# atmega.net
KiCad netlist of a schematic drawn in Altium Designer
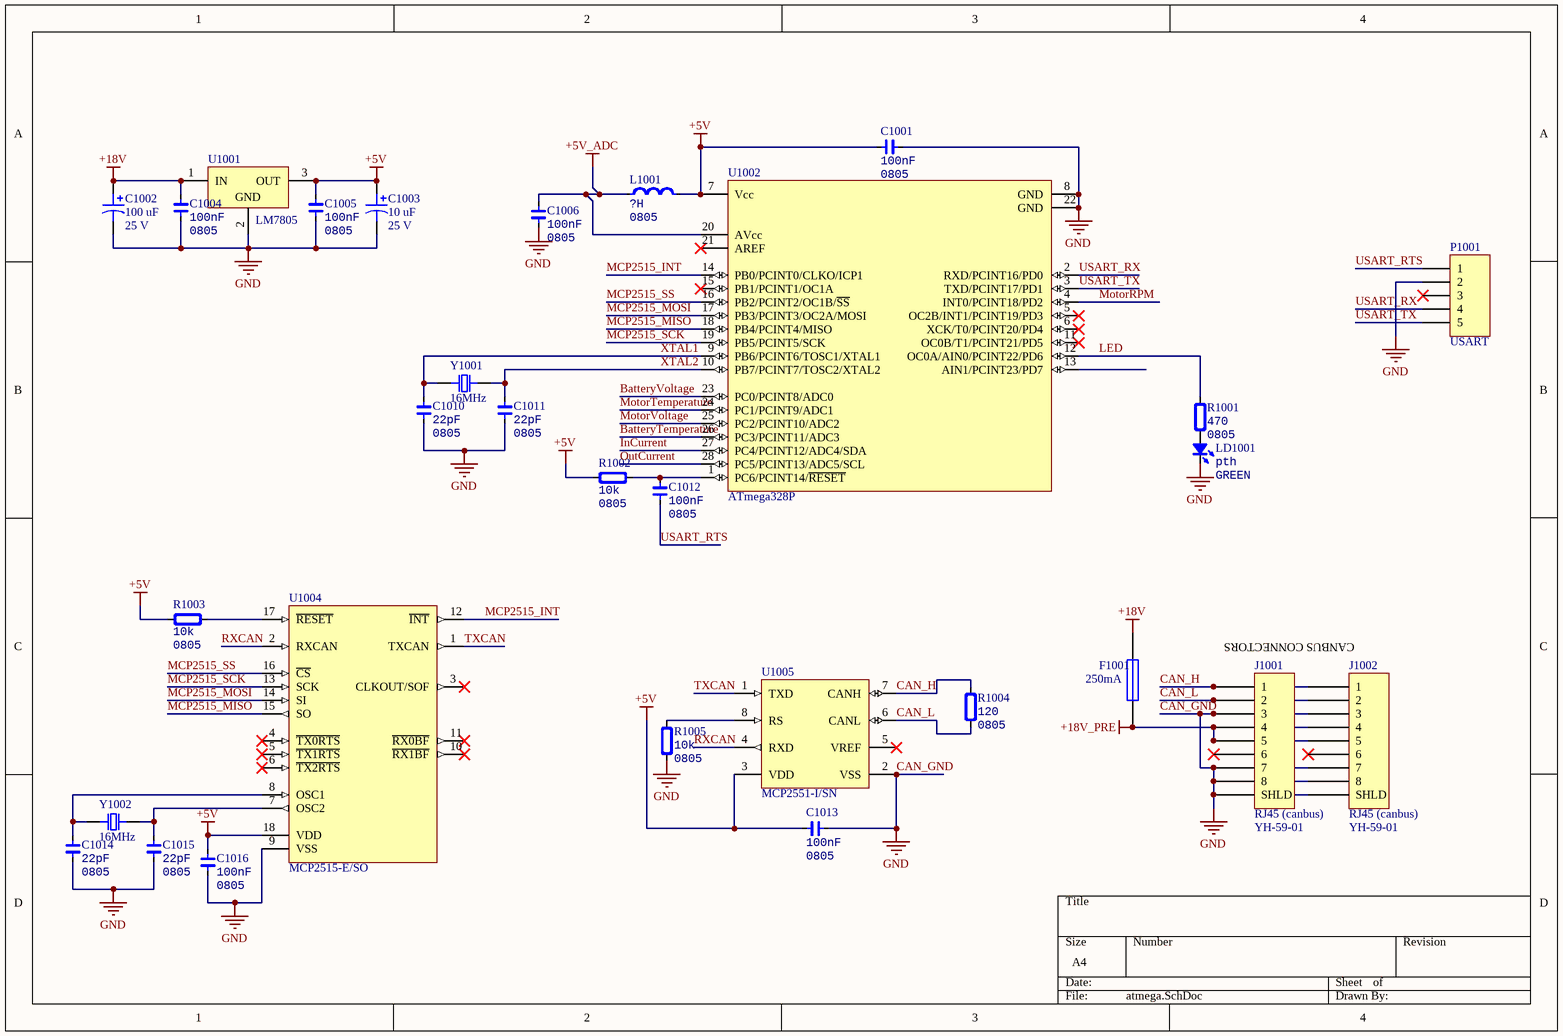
[diagram p0: atmega.SchDoc]

(export (version "E")
  (design (tool "Eeschema 10.0.6"))
  (components
    (comp (ref "C1001")
      (value "100nF")
      (footprint "Zenite_Footprints:0805C")
      (description "Capacitor")
      (fields (field (name "TYPE") "0805"))
      (libsource (lib "") (part "Cap_0805_1"))
    )
    (comp (ref "C1002")
      (value "100 uF")
      (footprint "CP3.5mm-8.0mm")
      (description "Solid Aluminum Capacitor with Organic Semiconductor Electrolyte: 100uF, 10V, Bulk Pack")
      (fields (field (name "VOLTAGE") "25 V") (field (name "Comment") "CapacitorPol"))
      (libsource (lib "R2R - Nova") (part "CapacitorPol"))
    )
    (comp (ref "C1003")
      (value "10 uF")
      (footprint "CP3.5mm-8.0mm")
      (description "Solid Aluminum Capacitor with Organic Semiconductor Electrolyte: 100uF, 10V, Bulk Pack")
      (fields (field (name "VOLTAGE") "25 V") (field (name "Comment") "CapacitorPol"))
      (libsource (lib "R2R - Nova") (part "CapacitorPol"))
    )
    (comp (ref "C1004")
      (value "100nF")
      (footprint "Zenite_Footprints:0805C")
      (description "Capacitor")
      (fields (field (name "TYPE") "0805"))
      (libsource (lib "SCH_Passive") (part "Cap_0805"))
    )
    (comp (ref "C1005")
      (value "100nF")
      (footprint "Zenite_Footprints:0805C")
      (description "Capacitor")
      (fields (field (name "TYPE") "0805"))
      (libsource (lib "SCH_Passive") (part "Cap_0805"))
    )
    (comp (ref "C1006")
      (value "100nF")
      (footprint "Zenite_Footprints:0805C")
      (description "Capacitor")
      (fields (field (name "TYPE") "0805"))
      (libsource (lib "SCH_Passive") (part "Cap_0805"))
    )
    (comp (ref "C1010")
      (value "22pF")
      (footprint "Zenite_Footprints:0805C")
      (description "Capacitor")
      (fields (field (name "TYPE") "0805"))
      (libsource (lib "SCH_Passive") (part "Cap_0805"))
    )
    (comp (ref "C1011")
      (value "22pF")
      (footprint "Zenite_Footprints:0805C")
      (description "Capacitor")
      (fields (field (name "TYPE") "0805"))
      (libsource (lib "SCH_Passive") (part "Cap_0805"))
    )
    (comp (ref "C1012")
      (value "100nF")
      (footprint "Zenite_Footprints:0805C")
      (description "Capacitor")
      (fields (field (name "TYPE") "0805"))
      (libsource (lib "") (part "Cap_0805_2"))
    )
    (comp (ref "C1013")
      (value "100nF")
      (footprint "Zenite_Footprints:0805C")
      (description "Capacitor")
      (fields (field (name "TYPE") "0805"))
      (libsource (lib "") (part "Cap_0805_1"))
    )
    (comp (ref "C1014")
      (value "22pF")
      (footprint "Zenite_Footprints:0805C")
      (description "Capacitor")
      (fields (field (name "TYPE") "0805"))
      (libsource (lib "SCH_Passive") (part "Cap_0805"))
    )
    (comp (ref "C1015")
      (value "22pF")
      (footprint "Zenite_Footprints:0805C")
      (description "Capacitor")
      (fields (field (name "TYPE") "0805"))
      (libsource (lib "SCH_Passive") (part "Cap_0805"))
    )
    (comp (ref "C1016")
      (value "100nF")
      (footprint "Zenite_Footprints:0805C")
      (description "Capacitor")
      (fields (field (name "TYPE") "0805"))
      (libsource (lib "") (part "Cap_0805_2"))
    )
    (comp (ref "F1001")
      (value "250mA")
      (footprint "Porta Fusivel")
      (description "Fuse")
      (libsource (lib "Miscellaneous Devices") (part "Fuse 1"))
    )
    (comp (ref "J1001")
      (value "RJ45 (canbus)")
      (footprint "ASSMANN A-2004-2-4-LP/FS")
      (description "YH-59-01")
      (fields (field (name "ALTIUM_VALUE") "YH-59-01"))
      (libsource (lib "Connectors") (part "Modular Jack with Shield"))
    )
    (comp (ref "J1002")
      (value "RJ45 (canbus)")
      (footprint "ASSMANN A-2004-2-4-LP/FS")
      (description "YH-59-01")
      (fields (field (name "ALTIUM_VALUE") "YH-59-01"))
      (libsource (lib "Connectors") (part "Modular Jack with Shield"))
    )
    (comp (ref "L1001")
      (value "?H")
      (footprint "Zenite_Footprints:0805L")
      (description "Inductor")
      (fields (field (name "TYPE") "0805"))
      (libsource (lib "SCH_Passive") (part "Ind_0805"))
    )
    (comp (ref "LD1001")
      (value "GREEN")
      (footprint "LED3MM")
      (description "LED")
      (fields (field (name "TYPE") "pth"))
      (libsource (lib "SCH_Active") (part "LED_0805"))
    )
    (comp (ref "P1001")
      (value "USART")
      (footprint "Zenite_Footprints:HDR1X5")
      (description "Header, 5-Pin")
      (libsource (lib "R2R - Nova") (part "Header 5"))
    )
    (comp (ref "R1001")
      (value "470")
      (footprint "Zenite_Footprints:0805R")
      (description "Resistor")
      (fields (field (name "TYPE") "0805"))
      (libsource (lib "SCH_Passive") (part "Res_0805"))
    )
    (comp (ref "R1002")
      (value "10k")
      (footprint "Zenite_Footprints:0805R")
      (description "Resistor")
      (fields (field (name "TYPE") "0805"))
      (libsource (lib "SCH_Passive") (part "Res_0805"))
    )
    (comp (ref "R1003")
      (value "10k")
      (footprint "Zenite_Footprints:0805R")
      (description "Resistor")
      (fields (field (name "TYPE") "0805"))
      (libsource (lib "SCH_Passive") (part "Res_0805"))
    )
    (comp (ref "R1004")
      (value "120")
      (footprint "Zenite_Footprints:0805R")
      (description "Resistor")
      (fields (field (name "TYPE") "0805"))
      (libsource (lib "SCH_Passive") (part "Res_0805"))
    )
    (comp (ref "R1005")
      (value "10k")
      (footprint "Zenite_Footprints:0805R")
      (description "Resistor")
      (fields (field (name "TYPE") "0805"))
      (libsource (lib "SCH_Passive") (part "Res_0805"))
    )
    (comp (ref "U1001")
      (value "LM7805")
      (footprint "TO220_deitado")
      (description "Positive-Voltage Regulator")
      (libsource (lib "TI Power Mgt Voltage Regulator") (part "µA7805CKC"))
    )
    (comp (ref "U1002")
      (value "ATmega328P")
      (footprint "DIP28-300(100)")
      (libsource (lib "R2R - Nova") (part "ATmega328P"))
    )
    (comp (ref "U1004")
      (value "MCP2515-E/SO")
      (footprint "WSO18_L")
      (description "Stand-Alone CAN Controller With SPI Interface, 18-Pin SOIC, Extended Temperature")
      (libsource (lib "Altium Content Vault") (part "COM-CAN-MCP2515-18"))
    )
    (comp (ref "U1005")
      (value "MCP2551-I/SN")
      (footprint "SOIC08-150(50)")
      (libsource (lib "Altium Content Vault") (part "MCHP-MCP2551-SN8"))
    )
    (comp (ref "Y1001")
      (value "16MHz")
      (footprint "HC49-US-THT")
      (description "Crystal")
      (libsource (lib "R2R - Nova") (part "Crystal"))
    )
    (comp (ref "Y1002")
      (value "16MHz")
      (footprint "HC49-US-THT")
      (description "Crystal")
      (libsource (lib "R2R - Nova") (part "Crystal"))
    )
  )
  (nets
    (net (code "1") (name "+5V") (class "Default")
      (node (ref "C1001") (pin "1") (pinfunction "1_1") (pintype "passive"))
      (node (ref "C1003") (pin "1") (pinfunction "1_1") (pintype "passive"))
      (node (ref "C1005") (pin "2") (pinfunction "2_2") (pintype "passive"))
      (node (ref "C1013") (pin "1") (pinfunction "1_1") (pintype "passive"))
      (node (ref "C1016") (pin "1") (pinfunction "1_1") (pintype "passive"))
      (node (ref "L1001") (pin "2") (pinfunction "2_2") (pintype "passive"))
      (node (ref "R1002") (pin "1") (pinfunction "1_1") (pintype "passive"))
      (node (ref "R1003") (pin "1") (pinfunction "1_1") (pintype "passive"))
      (node (ref "U1001") (pin "3") (pinfunction "OUT_3") (pintype "power_in"))
      (node (ref "U1002") (pin "7") (pinfunction "Vcc_7") (pintype "passive"))
      (node (ref "U1004") (pin "18") (pinfunction "VDD_18") (pintype "power_in"))
      (node (ref "U1005") (pin "3") (pinfunction "VDD_3") (pintype "power_in"))
    )
    (net (code "2") (name "+5V_ADC") (class "Default")
      (node (ref "C1006") (pin "2") (pinfunction "2_2") (pintype "passive"))
      (node (ref "L1001") (pin "1") (pinfunction "1_1") (pintype "passive"))
      (node (ref "U1002") (pin "20") (pinfunction "AVcc_20") (pintype "passive"))
    )
    (net (code "3") (name "+18V") (class "Default")
      (node (ref "C1002") (pin "1") (pinfunction "1_1") (pintype "passive"))
      (node (ref "C1004") (pin "2") (pinfunction "2_2") (pintype "passive"))
      (node (ref "F1001") (pin "1") (pinfunction "1_1") (pintype "passive"))
      (node (ref "U1001") (pin "1") (pinfunction "IN_1") (pintype "power_in"))
    )
    (net (code "4") (name "+18V_PRE") (class "Default")
      (node (ref "F1001") (pin "2") (pinfunction "2_2") (pintype "passive"))
      (node (ref "J1001") (pin "4") (pinfunction "4_4") (pintype "passive"))
      (node (ref "J1001") (pin "5") (pinfunction "5_5") (pintype "passive"))
      (node (ref "J1002") (pin "4") (pinfunction "4_4") (pintype "passive"))
      (node (ref "J1002") (pin "5") (pinfunction "5_5") (pintype "passive"))
    )
    (net (code "5") (name "/BatteryTemperature") (class "Default")
      (node (ref "U1002") (pin "26") (pinfunction "PC3/PCINT11/ADC3_26") (pintype "bidirectional"))
    )
    (net (code "6") (name "/BatteryVoltage") (class "Default")
      (node (ref "U1002") (pin "23") (pinfunction "PC0/PCINT8/ADC0_23") (pintype "bidirectional"))
    )
    (net (code "7") (name "/CAN_H") (class "Default")
      (node (ref "J1001") (pin "1") (pinfunction "1_1") (pintype "passive"))
      (node (ref "J1002") (pin "1") (pinfunction "1_1") (pintype "passive"))
      (node (ref "R1004") (pin "2") (pinfunction "2_2") (pintype "passive"))
      (node (ref "U1005") (pin "7") (pinfunction "CANH_7") (pintype "bidirectional"))
    )
    (net (code "8") (name "/CAN_L") (class "Default")
      (node (ref "J1001") (pin "2") (pinfunction "2_2") (pintype "passive"))
      (node (ref "J1002") (pin "2") (pinfunction "2_2") (pintype "passive"))
      (node (ref "R1004") (pin "1") (pinfunction "1_1") (pintype "passive"))
      (node (ref "U1005") (pin "6") (pinfunction "CANL_6") (pintype "bidirectional"))
    )
    (net (code "9") (name "/InCurrent") (class "Default")
      (node (ref "U1002") (pin "27") (pinfunction "PC4/PCINT12/ADC4/SDA_27") (pintype "bidirectional"))
    )
    (net (code "10") (name "/LED") (class "Default")
      (node (ref "R1001") (pin "2") (pinfunction "2_2") (pintype "passive"))
      (node (ref "U1002") (pin "12") (pinfunction "OC0A/AIN0/PCINT22/PD6_12") (pintype "bidirectional"))
    )
    (net (code "11") (name "/MCP2515_INT") (class "Default")
      (node (ref "U1002") (pin "14") (pinfunction "PB0/PCINT0/CLKO/ICP1_14") (pintype "bidirectional"))
      (node (ref "U1004") (pin "12") (pinfunction "~{INT}_12") (pintype "output"))
    )
    (net (code "12") (name "/MCP2515_MISO") (class "Default")
      (node (ref "U1002") (pin "18") (pinfunction "PB4/PCINT4/MISO_18") (pintype "bidirectional"))
      (node (ref "U1004") (pin "15") (pinfunction "SO_15") (pintype "output"))
    )
    (net (code "13") (name "/MCP2515_MOSI") (class "Default")
      (node (ref "U1002") (pin "17") (pinfunction "PB3/PCINT3/OC2A/MOSI_17") (pintype "bidirectional"))
      (node (ref "U1004") (pin "14") (pinfunction "SI_14") (pintype "input"))
    )
    (net (code "14") (name "/MCP2515_SCK") (class "Default")
      (node (ref "U1002") (pin "19") (pinfunction "PB5/PCINT5/SCK_19") (pintype "bidirectional"))
      (node (ref "U1004") (pin "13") (pinfunction "SCK_13") (pintype "input"))
    )
    (net (code "15") (name "/MCP2515_SS") (class "Default")
      (node (ref "U1002") (pin "16") (pinfunction "PB2/PCINT2/OC1B/~{SS}_16") (pintype "bidirectional"))
      (node (ref "U1004") (pin "16") (pinfunction "~{CS}_16") (pintype "input"))
    )
    (net (code "16") (name "/MotorRPM") (class "Default")
      (node (ref "U1002") (pin "4") (pinfunction "INT0/PCINT18/PD2_4") (pintype "bidirectional"))
    )
    (net (code "17") (name "/MotorTemperature") (class "Default")
      (node (ref "U1002") (pin "24") (pinfunction "PC1/PCINT9/ADC1_24") (pintype "bidirectional"))
    )
    (net (code "18") (name "/MotorVoltage") (class "Default")
      (node (ref "U1002") (pin "25") (pinfunction "PC2/PCINT10/ADC2_25") (pintype "bidirectional"))
    )
    (net (code "19") (name "/OutCurrent") (class "Default")
      (node (ref "U1002") (pin "28") (pinfunction "PC5/PCINT13/ADC5/SCL_28") (pintype "bidirectional"))
    )
    (net (code "20") (name "/RXCAN") (class "Default")
      (node (ref "U1004") (pin "2") (pinfunction "RXCAN_2") (pintype "input"))
      (node (ref "U1005") (pin "4") (pinfunction "RXD_4") (pintype "output"))
    )
    (net (code "21") (name "/TXCAN") (class "Default")
      (node (ref "U1004") (pin "1") (pinfunction "TXCAN_1") (pintype "output"))
      (node (ref "U1005") (pin "1") (pinfunction "TXD_1") (pintype "input"))
    )
    (net (code "22") (name "/USART_RTS") (class "Default")
      (node (ref "C1012") (pin "2") (pinfunction "2_2") (pintype "passive"))
      (node (ref "P1001") (pin "1") (pinfunction "1_1") (pintype "passive"))
    )
    (net (code "23") (name "/USART_RX") (class "Default")
      (node (ref "P1001") (pin "4") (pinfunction "4_4") (pintype "passive"))
      (node (ref "U1002") (pin "2") (pinfunction "RXD/PCINT16/PD0_2") (pintype "bidirectional"))
    )
    (net (code "24") (name "/USART_TX") (class "Default")
      (node (ref "P1001") (pin "5") (pinfunction "5_5") (pintype "passive"))
      (node (ref "U1002") (pin "3") (pinfunction "TXD/PCINT17/PD1_3") (pintype "bidirectional"))
    )
    (net (code "25") (name "/XTAL1") (class "Default")
      (node (ref "C1010") (pin "2") (pinfunction "2_2") (pintype "passive"))
      (node (ref "U1002") (pin "9") (pinfunction "PB6/PCINT6/TOSC1/XTAL1_9") (pintype "bidirectional"))
      (node (ref "Y1001") (pin "1") (pinfunction "1_1") (pintype "passive"))
    )
    (net (code "26") (name "/XTAL2") (class "Default")
      (node (ref "C1011") (pin "2") (pinfunction "2_2") (pintype "passive"))
      (node (ref "U1002") (pin "10") (pinfunction "PB7/PCINT7/TOSC2/XTAL2_10") (pintype "bidirectional"))
      (node (ref "Y1001") (pin "2") (pinfunction "2_2") (pintype "passive"))
    )
    (net (code "27") (name "GND") (class "Default")
      (node (ref "C1001") (pin "2") (pinfunction "2_2") (pintype "passive"))
      (node (ref "C1002") (pin "2") (pinfunction "2_2") (pintype "passive"))
      (node (ref "C1003") (pin "2") (pinfunction "2_2") (pintype "passive"))
      (node (ref "C1004") (pin "1") (pinfunction "1_1") (pintype "passive"))
      (node (ref "C1005") (pin "1") (pinfunction "1_1") (pintype "passive"))
      (node (ref "C1006") (pin "1") (pinfunction "1_1") (pintype "passive"))
      (node (ref "C1010") (pin "1") (pinfunction "1_1") (pintype "passive"))
      (node (ref "C1011") (pin "1") (pinfunction "1_1") (pintype "passive"))
      (node (ref "C1013") (pin "2") (pinfunction "2_2") (pintype "passive"))
      (node (ref "C1014") (pin "1") (pinfunction "1_1") (pintype "passive"))
      (node (ref "C1015") (pin "1") (pinfunction "1_1") (pintype "passive"))
      (node (ref "C1016") (pin "2") (pinfunction "2_2") (pintype "passive"))
      (node (ref "J1001") (pin "3") (pinfunction "3_3") (pintype "passive"))
      (node (ref "J1001") (pin "7") (pinfunction "7_7") (pintype "passive"))
      (node (ref "J1001") (pin "8") (pinfunction "8_8") (pintype "passive"))
      (node (ref "J1001") (pin "S") (pinfunction "SHLD_S") (pintype "passive"))
      (node (ref "J1002") (pin "3") (pinfunction "3_3") (pintype "passive"))
      (node (ref "J1002") (pin "7") (pinfunction "7_7") (pintype "passive"))
      (node (ref "J1002") (pin "8") (pinfunction "8_8") (pintype "passive"))
      (node (ref "J1002") (pin "S") (pinfunction "SHLD_S") (pintype "passive"))
      (node (ref "LD1001") (pin "2") (pinfunction "K_2") (pintype "passive"))
      (node (ref "P1001") (pin "2") (pinfunction "2_2") (pintype "passive"))
      (node (ref "R1005") (pin "2") (pinfunction "2_2") (pintype "passive"))
      (node (ref "U1001") (pin "2") (pinfunction "GND_2") (pintype "power_in"))
      (node (ref "U1002") (pin "22") (pinfunction "GND_22") (pintype "passive"))
      (node (ref "U1002") (pin "8") (pinfunction "GND_8") (pintype "passive"))
      (node (ref "U1004") (pin "9") (pinfunction "VSS_9") (pintype "power_in"))
      (node (ref "U1005") (pin "2") (pinfunction "VSS_2") (pintype "power_in"))
    )
    (net (code "28") (name "Net-(LD1001-A)") (class "Default")
      (node (ref "LD1001") (pin "1") (pinfunction "A_1") (pintype "passive"))
      (node (ref "R1001") (pin "1") (pinfunction "1_1") (pintype "passive"))
    )
    (net (code "29") (name "Net-(U1002-PC6{slash}PCINT14{slash}~{RESET})") (class "Default")
      (node (ref "C1012") (pin "1") (pinfunction "1_1") (pintype "passive"))
      (node (ref "R1002") (pin "2") (pinfunction "2_2") (pintype "passive"))
      (node (ref "U1002") (pin "1") (pinfunction "PC6/PCINT14/~{RESET}_1") (pintype "bidirectional"))
    )
    (net (code "30") (name "Net-(U1004-OSC1)") (class "Default")
      (node (ref "C1014") (pin "2") (pinfunction "2_2") (pintype "passive"))
      (node (ref "U1004") (pin "8") (pinfunction "OSC1_8") (pintype "input"))
      (node (ref "Y1002") (pin "1") (pinfunction "1_1") (pintype "passive"))
    )
    (net (code "31") (name "Net-(U1004-OSC2)") (class "Default")
      (node (ref "C1015") (pin "2") (pinfunction "2_2") (pintype "passive"))
      (node (ref "U1004") (pin "7") (pinfunction "OSC2_7") (pintype "output"))
      (node (ref "Y1002") (pin "2") (pinfunction "2_2") (pintype "passive"))
    )
    (net (code "32") (name "Net-(U1004-~{RESET})") (class "Default")
      (node (ref "R1003") (pin "2") (pinfunction "2_2") (pintype "passive"))
      (node (ref "U1004") (pin "17") (pinfunction "~{RESET}_17") (pintype "input"))
    )
    (net (code "33") (name "Net-(U1005-RS)") (class "Default")
      (node (ref "R1005") (pin "1") (pinfunction "1_1") (pintype "passive"))
      (node (ref "U1005") (pin "8") (pinfunction "RS_8") (pintype "input"))
    )
    (net (code "34") (name "unconnected-(J1001-Pad6)") (class "Default")
      (node (ref "J1001") (pin "6") (pinfunction "6_6") (pintype "passive+no_connect"))
    )
    (net (code "35") (name "unconnected-(J1002-Pad6)") (class "Default")
      (node (ref "J1002") (pin "6") (pinfunction "6_6") (pintype "passive+no_connect"))
    )
    (net (code "36") (name "unconnected-(P1001-Pad3)") (class "Default")
      (node (ref "P1001") (pin "3") (pinfunction "3_3") (pintype "passive+no_connect"))
    )
    (net (code "37") (name "unconnected-(U1002-AIN1{slash}PCINT23{slash}PD7-Pad13)") (class "Default")
      (node (ref "U1002") (pin "13") (pinfunction "AIN1/PCINT23/PD7_13") (pintype "bidirectional"))
    )
    (net (code "38") (name "unconnected-(U1002-AREF-Pad21)") (class "Default")
      (node (ref "U1002") (pin "21") (pinfunction "AREF_21") (pintype "passive+no_connect"))
    )
    (net (code "39") (name "unconnected-(U1002-OC0B{slash}T1{slash}PCINT21{slash}PD5-Pad11)") (class "Default")
      (node (ref "U1002") (pin "11") (pinfunction "OC0B/T1/PCINT21/PD5_11") (pintype "bidirectional+no_connect"))
    )
    (net (code "40") (name "unconnected-(U1002-OC2B{slash}INT1{slash}PCINT19{slash}PD3-Pad5)") (class "Default")
      (node (ref "U1002") (pin "5") (pinfunction "OC2B/INT1/PCINT19/PD3_5") (pintype "bidirectional+no_connect"))
    )
    (net (code "41") (name "unconnected-(U1002-PB1{slash}PCINT1{slash}OC1A-Pad15)") (class "Default")
      (node (ref "U1002") (pin "15") (pinfunction "PB1/PCINT1/OC1A_15") (pintype "bidirectional+no_connect"))
    )
    (net (code "42") (name "unconnected-(U1002-XCK{slash}T0{slash}PCINT20{slash}PD4-Pad6)") (class "Default")
      (node (ref "U1002") (pin "6") (pinfunction "XCK/T0/PCINT20/PD4_6") (pintype "bidirectional+no_connect"))
    )
    (net (code "43") (name "unconnected-(U1004-CLKOUT{slash}SOF-Pad3)") (class "Default")
      (node (ref "U1004") (pin "3") (pinfunction "CLKOUT/SOF_3") (pintype "output+no_connect"))
    )
    (net (code "44") (name "unconnected-(U1004-~{RX0BF}-Pad11)") (class "Default")
      (node (ref "U1004") (pin "11") (pinfunction "~{RX0BF}_11") (pintype "output+no_connect"))
    )
    (net (code "45") (name "unconnected-(U1004-~{RX1BF}-Pad10)") (class "Default")
      (node (ref "U1004") (pin "10") (pinfunction "~{RX1BF}_10") (pintype "output+no_connect"))
    )
    (net (code "46") (name "unconnected-(U1004-~{TX0RTS}-Pad4)") (class "Default")
      (node (ref "U1004") (pin "4") (pinfunction "~{TX0RTS}_4") (pintype "input+no_connect"))
    )
    (net (code "47") (name "unconnected-(U1004-~{TX1RTS}-Pad5)") (class "Default")
      (node (ref "U1004") (pin "5") (pinfunction "~{TX1RTS}_5") (pintype "input+no_connect"))
    )
    (net (code "48") (name "unconnected-(U1004-~{TX2RTS}-Pad6)") (class "Default")
      (node (ref "U1004") (pin "6") (pinfunction "~{TX2RTS}_6") (pintype "input+no_connect"))
    )
    (net (code "49") (name "unconnected-(U1005-VREF-Pad5)") (class "Default")
      (node (ref "U1005") (pin "5") (pinfunction "VREF_5") (pintype "power_in+no_connect"))
    )
  )
)
